# EEPROM.net
KiCad netlist of a schematic drawn in Altium Designer
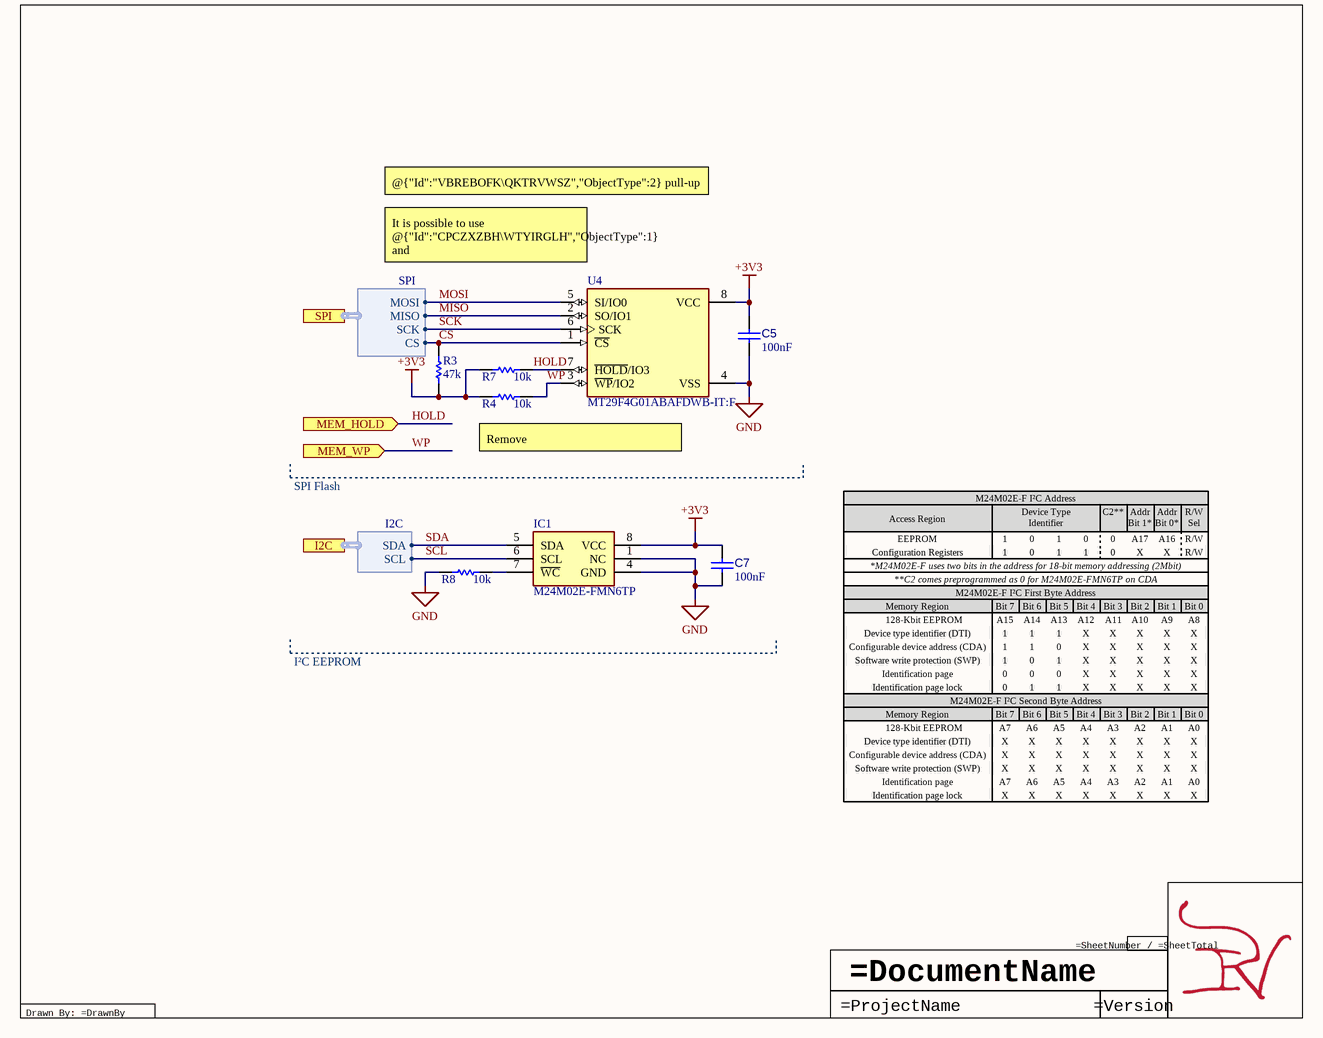
[diagram p0: EEPROM.SchDoc]

(export (version "E")
  (design (tool "Eeschema 10.0.6"))
  (components
    (comp (ref "C5")
      (value "100nF")
      (footprint "CAP 0402_1005")
      (fields (field (name "TOLERANCE") "10%") (field (name "Comment") "CAP-NP-2"))
      (libsource (lib "IIT Motorsports") (part "CAP-NP-2"))
    )
    (comp (ref "C7")
      (value "100nF")
      (footprint "CAP 0402_1005")
      (fields (field (name "TOLERANCE") "10%") (field (name "Comment") "CAP-NP-2"))
      (libsource (lib "IIT Motorsports") (part "CAP-NP-2"))
    )
    (comp (ref "IC1")
      (value "M24M02E-FMN6TP")
      (footprint "SOIC127P600X175-8N")
      (fields (field (name "MOUSER PART NUMBER") "511-M24M02E-FMN6TP"))
      (libsource (lib "IIT Motorsports") (part "M24M02E-FMN6TP"))
    )
    (comp (ref "R3")
      (value "47k")
      (footprint "RES 0402_1005")
      (fields
        (field (name "TOLERANCE") "1%")
        (field (name "POWER") "100mW")
        (field (name "Comment") "47k-0402-0.1/1")
      )
      (libsource (lib "IIT Motorsports") (part "RES"))
    )
    (comp (ref "R4")
      (value "10k")
      (footprint "RES 0402_1005")
      (fields
        (field (name "TOLERANCE") "1%")
        (field (name "POWER") "100mW")
        (field (name "Comment") "10K-0402-0.1/1")
      )
      (libsource (lib "IIT Motorsports") (part "RES"))
    )
    (comp (ref "R7")
      (value "10k")
      (footprint "RES 0402_1005")
      (fields
        (field (name "TOLERANCE") "1%")
        (field (name "POWER") "100mW")
        (field (name "Comment") "10K-0402-0.1/1")
      )
      (libsource (lib "IIT Motorsports") (part "RES"))
    )
    (comp (ref "R8")
      (value "10k")
      (footprint "RES 0402_1005")
      (fields
        (field (name "TOLERANCE") "1%")
        (field (name "POWER") "100mW")
        (field (name "Comment") "10K-0402-0.1/1")
      )
      (libsource (lib "IIT Motorsports") (part "RES"))
    )
    (comp (ref "U4")
      (value "MT29F4G01ABAFDWB-IT:F")
      (footprint "FP-WB-IPC_B")
      (description "SLC NAND Flash Serial-SPI 3.3V 4Gbit 4G X 1bit 5ns/6ns 8-Pin UPDFN Tray")
      (libsource (lib "IIT Motorsports") (part "2a22d8121842150c115fe802c55be1a"))
    )
  )
  (nets
    (net (code "3") (name "+3V3") (class "Default")
      (node (ref "C5") (pin "2") (pinfunction "2_2") (pintype "passive"))
      (node (ref "C7") (pin "2") (pinfunction "2_2") (pintype "passive"))
      (node (ref "IC1") (pin "8") (pinfunction "VCC_8") (pintype "passive"))
      (node (ref "R3") (pin "1") (pinfunction "1_1") (pintype "passive"))
      (node (ref "R4") (pin "1") (pinfunction "1_1") (pintype "passive"))
      (node (ref "R7") (pin "1") (pinfunction "1_1") (pintype "passive"))
      (node (ref "U4") (pin "8") (pinfunction "VCC_8") (pintype "power_in"))
    )
    (net (code "4") (name "/CS") (class "Default")
      (node (ref "R3") (pin "2") (pinfunction "2_2") (pintype "passive"))
      (node (ref "U4") (pin "1") (pinfunction "~{CS}_1") (pintype "input"))
    )
    (net (code "5") (name "/HOLD") (class "Default")
      (node (ref "R7") (pin "2") (pinfunction "2_2") (pintype "passive"))
      (node (ref "U4") (pin "7") (pinfunction "~{HOLD}/IO3_7") (pintype "bidirectional"))
    )
    (net (code "6") (name "/MISO") (class "Default")
      (node (ref "U4") (pin "2") (pinfunction "SO/IO1_2") (pintype "bidirectional"))
    )
    (net (code "7") (name "/MOSI") (class "Default")
      (node (ref "U4") (pin "5") (pinfunction "SI/IO0_5") (pintype "bidirectional"))
    )
    (net (code "8") (name "/SCK") (class "Default")
      (node (ref "U4") (pin "6") (pinfunction "SCK_6") (pintype "input"))
    )
    (net (code "9") (name "/SCL") (class "Default")
      (node (ref "IC1") (pin "6") (pinfunction "SCL_6") (pintype "passive"))
    )
    (net (code "10") (name "/SDA") (class "Default")
      (node (ref "IC1") (pin "5") (pinfunction "SDA_5") (pintype "passive"))
    )
    (net (code "11") (name "/WP") (class "Default")
      (node (ref "R4") (pin "2") (pinfunction "2_2") (pintype "passive"))
      (node (ref "U4") (pin "3") (pinfunction "~{WP}/IO2_3") (pintype "bidirectional"))
    )
    (net (code "14") (name "GND") (class "Default")
      (node (ref "C5") (pin "1") (pinfunction "1_1") (pintype "passive"))
      (node (ref "C7") (pin "1") (pinfunction "1_1") (pintype "passive"))
      (node (ref "IC1") (pin "1") (pinfunction "NC_1") (pintype "passive"))
      (node (ref "IC1") (pin "4") (pinfunction "GND_4") (pintype "passive"))
      (node (ref "R8") (pin "1") (pinfunction "1_1") (pintype "passive"))
      (node (ref "U4") (pin "4") (pinfunction "VSS_4") (pintype "power_in"))
    )
    (net (code "15") (name "Net-(IC1-~{WC})") (class "Default")
      (node (ref "IC1") (pin "7") (pinfunction "~{WC}_7") (pintype "passive"))
      (node (ref "R8") (pin "2") (pinfunction "2_2") (pintype "passive"))
    )
  )
)
